# 11_MIPI_DSI_CSI.net
KiCad netlist of a schematic drawn in Altium Designer
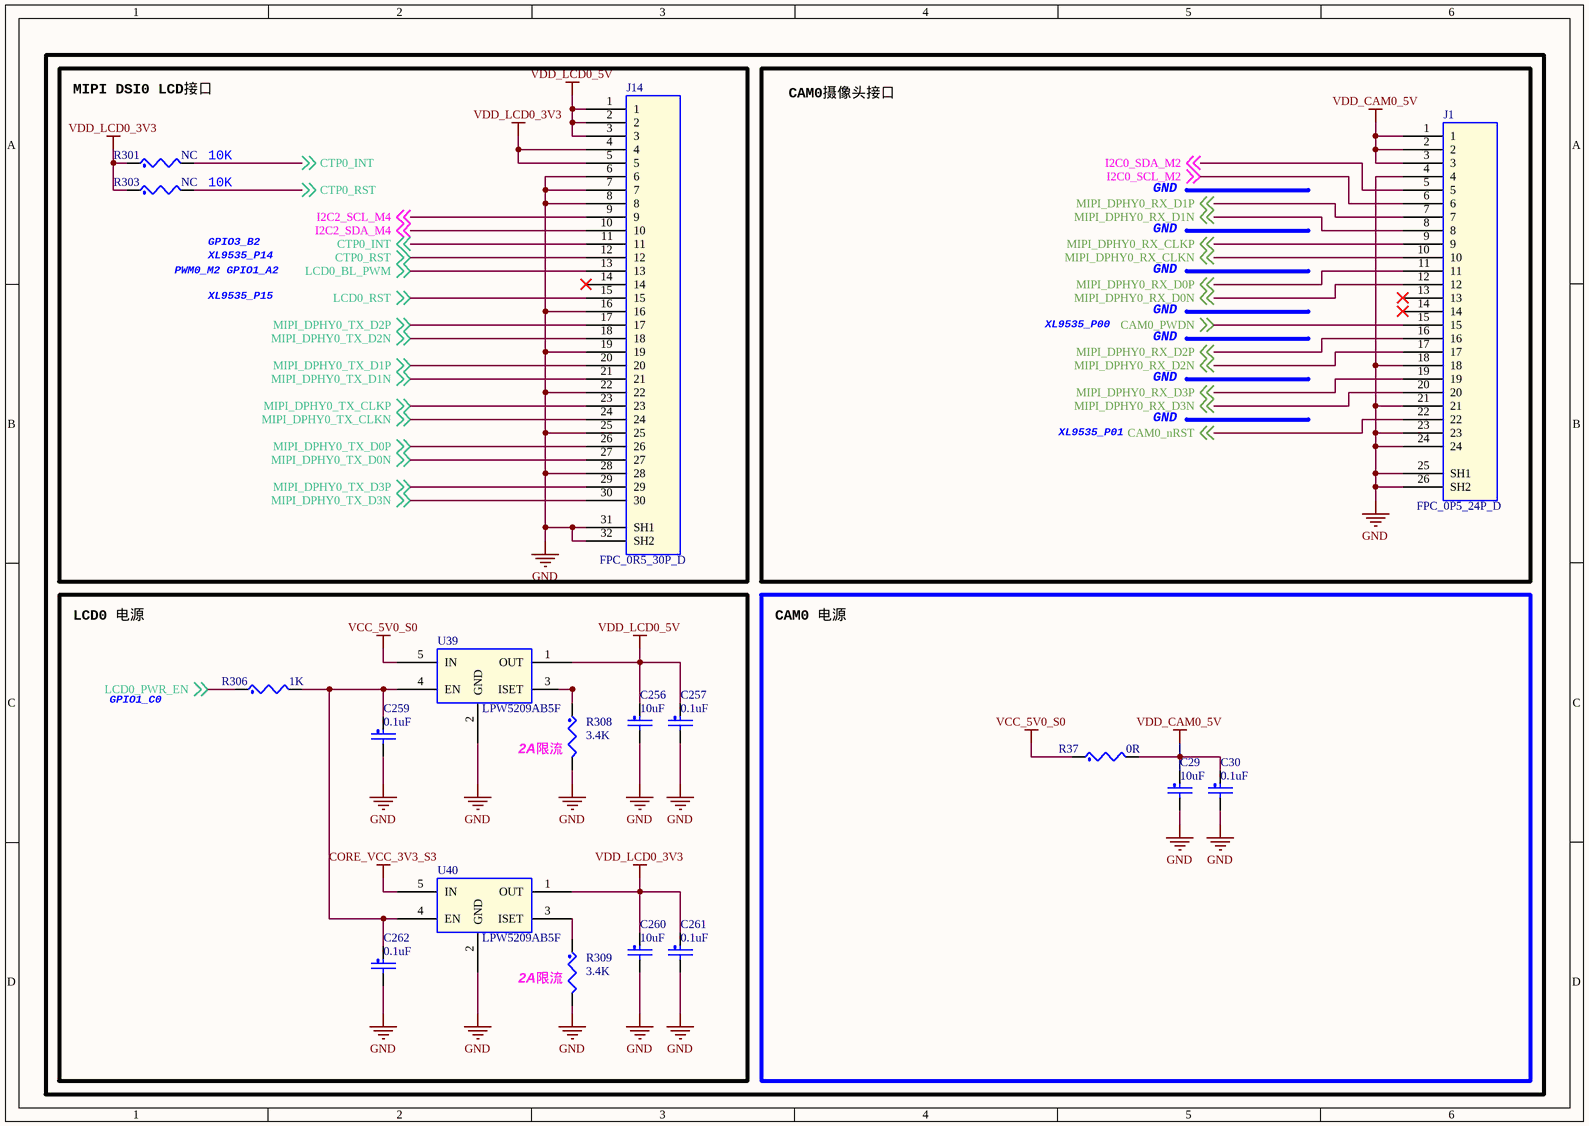
[diagram p0: 11.MIPI DSI_CSI.SchDoc]

(export (version "E")
  (design (tool "Eeschema 10.0.6"))
  (components
    (comp (ref "C29") (value "10uF") (footprint "0.PCB1:C0402") (libsource (lib "RK3588底板") (part "CAP_NP")))
    (comp (ref "C30") (value "0.1uF") (footprint "0.PCB1:C0402") (libsource (lib "RK3588底板") (part "CAP_NP")))
    (comp (ref "C256") (value "10uF") (footprint "0.PCB1:C0402") (libsource (lib "RK3588底板") (part "CAP_NP")))
    (comp (ref "C257")
      (value "0.1uF")
      (footprint "0.PCB1:C0402")
      (libsource (lib "RK3588底板") (part "CAP_NP"))
    )
    (comp (ref "C259")
      (value "0.1uF")
      (footprint "0.PCB1:C0402")
      (libsource (lib "RK3588底板") (part "CAP_NP"))
    )
    (comp (ref "C260") (value "10uF") (footprint "0.PCB1:C0402") (libsource (lib "RK3588底板") (part "CAP_NP")))
    (comp (ref "C261")
      (value "0.1uF")
      (footprint "0.PCB1:C0402")
      (libsource (lib "RK3588底板") (part "CAP_NP"))
    )
    (comp (ref "C262")
      (value "0.1uF")
      (footprint "0.PCB1:C0402")
      (libsource (lib "RK3588底板") (part "CAP_NP"))
    )
    (comp (ref "J1")
      (value "FPC_0P5_24P_D")
      (footprint "0.PCB1:fpc_24p_0p5")
      (libsource (lib "RK3588底板") (part "FPC-24P"))
    )
    (comp (ref "J14")
      (value "FPC_0R5_30P_D")
      (footprint "0.PCB1:FPC-30P-0P5")
      (libsource (lib "RK3588底板") (part "FPC-30P"))
    )
    (comp (ref "R37") (value "0R") (footprint "0.PCB1:R0402") (libsource (lib "RK3588底板") (part "RES")))
    (comp (ref "R301") (value "NC") (footprint "0.PCB1:R0402") (libsource (lib "RK3588底板") (part "RES")))
    (comp (ref "R303") (value "NC") (footprint "0.PCB1:R0402") (libsource (lib "RK3588底板") (part "RES")))
    (comp (ref "R306") (value "1K") (footprint "0.PCB1:R0402") (libsource (lib "RK3588底板") (part "RES")))
    (comp (ref "R308") (value "3.4K") (footprint "0.PCB1:R0402") (libsource (lib "RK3588底板") (part "RES")))
    (comp (ref "R309") (value "3.4K") (footprint "0.PCB1:R0402") (libsource (lib "RK3588底板") (part "RES")))
    (comp (ref "U39")
      (value "LPW5209AB5F")
      (footprint "0.PCB1:SOT23-5")
      (libsource (lib "RK3588底板") (part "LPW5209AB5F"))
    )
    (comp (ref "U40")
      (value "LPW5209AB5F")
      (footprint "0.PCB1:SOT23-5")
      (libsource (lib "RK3588底板") (part "LPW5209AB5F"))
    )
  )
  (nets
    (net (code "1") (name "CAM0_PWDN") (class "Default")
      (node (ref "J1") (pin "15") (pinfunction "15_15") (pintype "passive"))
    )
    (net (code "2") (name "CAM0_nRST") (class "Default")
      (node (ref "J1") (pin "22") (pinfunction "22_22") (pintype "passive"))
    )
    (net (code "3") (name "CORE_VCC_3V3_S3") (class "Default")
      (node (ref "U40") (pin "5") (pinfunction "IN_5") (pintype "passive"))
    )
    (net (code "4") (name "CTP0_INT") (class "Default")
      (node (ref "J14") (pin "11") (pinfunction "11_11") (pintype "passive"))
      (node (ref "R301") (pin "2") (pinfunction "2_2") (pintype "passive"))
    )
    (net (code "5") (name "CTP0_RST") (class "Default")
      (node (ref "J14") (pin "12") (pinfunction "12_12") (pintype "passive"))
      (node (ref "R303") (pin "2") (pinfunction "2_2") (pintype "passive"))
    )
    (net (code "6") (name "GND") (class "Default")
      (node (ref "C256") (pin "2") (pinfunction "2_2") (pintype "passive"))
      (node (ref "C257") (pin "2") (pinfunction "2_2") (pintype "passive"))
      (node (ref "C259") (pin "2") (pinfunction "2_2") (pintype "passive"))
      (node (ref "C260") (pin "2") (pinfunction "2_2") (pintype "passive"))
      (node (ref "C261") (pin "2") (pinfunction "2_2") (pintype "passive"))
      (node (ref "C262") (pin "2") (pinfunction "2_2") (pintype "passive"))
      (node (ref "C29") (pin "2") (pinfunction "2_2") (pintype "passive"))
      (node (ref "C30") (pin "2") (pinfunction "2_2") (pintype "passive"))
      (node (ref "J1") (pin "18") (pinfunction "18_18") (pintype "passive"))
      (node (ref "J1") (pin "21") (pinfunction "21_21") (pintype "passive"))
      (node (ref "J1") (pin "23") (pinfunction "23_23") (pintype "passive"))
      (node (ref "J1") (pin "24") (pinfunction "24_24") (pintype "passive"))
      (node (ref "J1") (pin "25") (pinfunction "SH1_25") (pintype "passive"))
      (node (ref "J1") (pin "26") (pinfunction "SH2_26") (pintype "passive"))
      (node (ref "J1") (pin "4") (pinfunction "4_4") (pintype "passive"))
      (node (ref "J14") (pin "16") (pinfunction "16_16") (pintype "passive"))
      (node (ref "J14") (pin "19") (pinfunction "19_19") (pintype "passive"))
      (node (ref "J14") (pin "22") (pinfunction "22_22") (pintype "passive"))
      (node (ref "J14") (pin "25") (pinfunction "25_25") (pintype "passive"))
      (node (ref "J14") (pin "28") (pinfunction "28_28") (pintype "passive"))
      (node (ref "J14") (pin "31") (pinfunction "SH1_31") (pintype "passive"))
      (node (ref "J14") (pin "32") (pinfunction "SH2_32") (pintype "passive"))
      (node (ref "J14") (pin "6") (pinfunction "6_6") (pintype "passive"))
      (node (ref "J14") (pin "7") (pinfunction "7_7") (pintype "passive"))
      (node (ref "J14") (pin "8") (pinfunction "8_8") (pintype "passive"))
      (node (ref "R308") (pin "2") (pinfunction "2_2") (pintype "passive"))
      (node (ref "R309") (pin "2") (pinfunction "2_2") (pintype "passive"))
      (node (ref "U39") (pin "2") (pinfunction "GND_2") (pintype "passive"))
      (node (ref "U40") (pin "2") (pinfunction "GND_2") (pintype "passive"))
    )
    (net (code "7") (name "I2C0_SCL_M2") (class "Default")
      (node (ref "J1") (pin "6") (pinfunction "6_6") (pintype "passive"))
    )
    (net (code "8") (name "I2C0_SDA_M2") (class "Default")
      (node (ref "J1") (pin "5") (pinfunction "5_5") (pintype "passive"))
    )
    (net (code "9") (name "I2C2_SCL_M4") (class "Default")
      (node (ref "J14") (pin "9") (pinfunction "9_9") (pintype "passive"))
    )
    (net (code "10") (name "I2C2_SDA_M4") (class "Default")
      (node (ref "J14") (pin "10") (pinfunction "10_10") (pintype "passive"))
    )
    (net (code "11") (name "LCD0_BL_PWM") (class "Default")
      (node (ref "J14") (pin "13") (pinfunction "13_13") (pintype "passive"))
    )
    (net (code "12") (name "LCD0_PWR_EN") (class "Default")
      (node (ref "R306") (pin "1") (pinfunction "1_1") (pintype "passive"))
    )
    (net (code "13") (name "LCD0_RST") (class "Default")
      (node (ref "J14") (pin "15") (pinfunction "15_15") (pintype "passive"))
    )
    (net (code "14") (name "MIPI_DPHY0_RX_CLKN") (class "Default")
      (node (ref "J1") (pin "10") (pinfunction "10_10") (pintype "passive"))
    )
    (net (code "15") (name "MIPI_DPHY0_RX_CLKP") (class "Default")
      (node (ref "J1") (pin "9") (pinfunction "9_9") (pintype "passive"))
    )
    (net (code "16") (name "MIPI_DPHY0_RX_D0N") (class "Default")
      (node (ref "J1") (pin "12") (pinfunction "12_12") (pintype "passive"))
    )
    (net (code "17") (name "MIPI_DPHY0_RX_D0P") (class "Default")
      (node (ref "J1") (pin "11") (pinfunction "11_11") (pintype "passive"))
    )
    (net (code "18") (name "MIPI_DPHY0_RX_D1N") (class "Default")
      (node (ref "J1") (pin "8") (pinfunction "8_8") (pintype "passive"))
    )
    (net (code "19") (name "MIPI_DPHY0_RX_D1P") (class "Default")
      (node (ref "J1") (pin "7") (pinfunction "7_7") (pintype "passive"))
    )
    (net (code "20") (name "MIPI_DPHY0_RX_D2N") (class "Default")
      (node (ref "J1") (pin "17") (pinfunction "17_17") (pintype "passive"))
    )
    (net (code "21") (name "MIPI_DPHY0_RX_D2P") (class "Default")
      (node (ref "J1") (pin "16") (pinfunction "16_16") (pintype "passive"))
    )
    (net (code "22") (name "MIPI_DPHY0_RX_D3N") (class "Default")
      (node (ref "J1") (pin "20") (pinfunction "20_20") (pintype "passive"))
    )
    (net (code "23") (name "MIPI_DPHY0_RX_D3P") (class "Default")
      (node (ref "J1") (pin "19") (pinfunction "19_19") (pintype "passive"))
    )
    (net (code "24") (name "MIPI_DPHY0_TX_CLKN") (class "Default")
      (node (ref "J14") (pin "24") (pinfunction "24_24") (pintype "passive"))
    )
    (net (code "25") (name "MIPI_DPHY0_TX_CLKP") (class "Default")
      (node (ref "J14") (pin "23") (pinfunction "23_23") (pintype "passive"))
    )
    (net (code "26") (name "MIPI_DPHY0_TX_D0N") (class "Default")
      (node (ref "J14") (pin "27") (pinfunction "27_27") (pintype "passive"))
    )
    (net (code "27") (name "MIPI_DPHY0_TX_D0P") (class "Default")
      (node (ref "J14") (pin "26") (pinfunction "26_26") (pintype "passive"))
    )
    (net (code "28") (name "MIPI_DPHY0_TX_D1N") (class "Default")
      (node (ref "J14") (pin "21") (pinfunction "21_21") (pintype "passive"))
    )
    (net (code "29") (name "MIPI_DPHY0_TX_D1P") (class "Default")
      (node (ref "J14") (pin "20") (pinfunction "20_20") (pintype "passive"))
    )
    (net (code "30") (name "MIPI_DPHY0_TX_D2N") (class "Default")
      (node (ref "J14") (pin "18") (pinfunction "18_18") (pintype "passive"))
    )
    (net (code "31") (name "MIPI_DPHY0_TX_D2P") (class "Default")
      (node (ref "J14") (pin "17") (pinfunction "17_17") (pintype "passive"))
    )
    (net (code "32") (name "MIPI_DPHY0_TX_D3N") (class "Default")
      (node (ref "J14") (pin "30") (pinfunction "30_30") (pintype "passive"))
    )
    (net (code "33") (name "MIPI_DPHY0_TX_D3P") (class "Default")
      (node (ref "J14") (pin "29") (pinfunction "29_29") (pintype "passive"))
    )
    (net (code "34") (name "Net-(U39-EN)") (class "Default")
      (node (ref "C259") (pin "1") (pinfunction "1_1") (pintype "passive"))
      (node (ref "C262") (pin "1") (pinfunction "1_1") (pintype "passive"))
      (node (ref "R306") (pin "2") (pinfunction "2_2") (pintype "passive"))
      (node (ref "U39") (pin "4") (pinfunction "EN_4") (pintype "passive"))
      (node (ref "U40") (pin "4") (pinfunction "EN_4") (pintype "passive"))
    )
    (net (code "35") (name "Net-(U39-ISET)") (class "Default")
      (node (ref "R308") (pin "1") (pinfunction "1_1") (pintype "passive"))
      (node (ref "U39") (pin "3") (pinfunction "ISET_3") (pintype "passive"))
    )
    (net (code "36") (name "Net-(U40-ISET)") (class "Default")
      (node (ref "R309") (pin "1") (pinfunction "1_1") (pintype "passive"))
      (node (ref "U40") (pin "3") (pinfunction "ISET_3") (pintype "passive"))
    )
    (net (code "37") (name "VCC_5V0_S0") (class "Default")
      (node (ref "R37") (pin "1") (pinfunction "1_1") (pintype "passive"))
      (node (ref "U39") (pin "5") (pinfunction "IN_5") (pintype "passive"))
    )
    (net (code "38") (name "VDD_CAM0_5V") (class "Default")
      (node (ref "C29") (pin "1") (pinfunction "1_1") (pintype "passive"))
      (node (ref "C30") (pin "1") (pinfunction "1_1") (pintype "passive"))
      (node (ref "J1") (pin "1") (pinfunction "1_1") (pintype "passive"))
      (node (ref "J1") (pin "2") (pinfunction "2_2") (pintype "passive"))
      (node (ref "J1") (pin "3") (pinfunction "3_3") (pintype "passive"))
      (node (ref "R37") (pin "2") (pinfunction "2_2") (pintype "passive"))
    )
    (net (code "39") (name "VDD_LCD0_3V3") (class "Default")
      (node (ref "C260") (pin "1") (pinfunction "1_1") (pintype "passive"))
      (node (ref "C261") (pin "1") (pinfunction "1_1") (pintype "passive"))
      (node (ref "J14") (pin "4") (pinfunction "4_4") (pintype "passive"))
      (node (ref "J14") (pin "5") (pinfunction "5_5") (pintype "passive"))
      (node (ref "R301") (pin "1") (pinfunction "1_1") (pintype "passive"))
      (node (ref "R303") (pin "1") (pinfunction "1_1") (pintype "passive"))
      (node (ref "U40") (pin "1") (pinfunction "OUT_1") (pintype "passive"))
    )
    (net (code "40") (name "VDD_LCD0_5V") (class "Default")
      (node (ref "C256") (pin "1") (pinfunction "1_1") (pintype "passive"))
      (node (ref "C257") (pin "1") (pinfunction "1_1") (pintype "passive"))
      (node (ref "J14") (pin "1") (pinfunction "1_1") (pintype "passive"))
      (node (ref "J14") (pin "2") (pinfunction "2_2") (pintype "passive"))
      (node (ref "J14") (pin "3") (pinfunction "3_3") (pintype "passive"))
      (node (ref "U39") (pin "1") (pinfunction "OUT_1") (pintype "passive"))
    )
    (net (code "41") (name "unconnected-(J1-Pad13)") (class "Default")
      (node (ref "J1") (pin "13") (pinfunction "13_13") (pintype "passive+no_connect"))
    )
    (net (code "42") (name "unconnected-(J1-Pad14)") (class "Default")
      (node (ref "J1") (pin "14") (pinfunction "14_14") (pintype "passive+no_connect"))
    )
    (net (code "43") (name "unconnected-(J14-Pad14)") (class "Default")
      (node (ref "J14") (pin "14") (pinfunction "14_14") (pintype "passive+no_connect"))
    )
  )
)
